# connector_fridge.net
KiCad netlist of a schematic drawn in Altium Designer
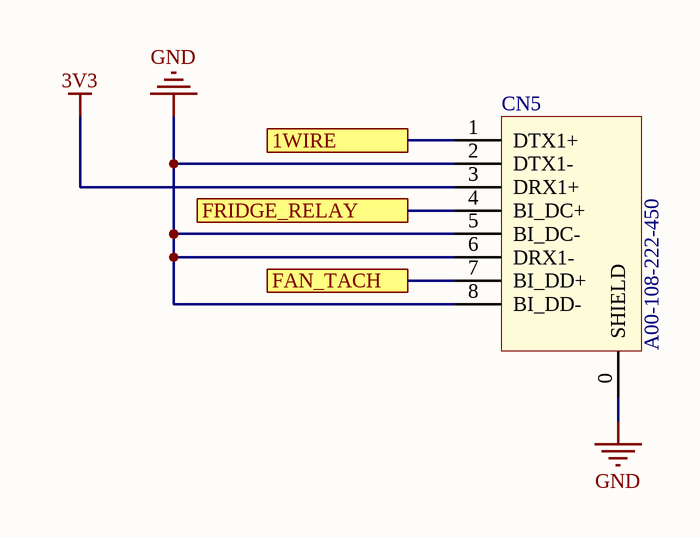
[diagram p0: connector_fridge.SchDoc]

(export (version "E")
  (design (tool "Eeschema 10.0.6"))
  (components
    (comp (ref "CN5")
      (value "CONN_RJ45_TOP_A00-108-222-450")
      (footprint "RJ45 TOP ENTRY EDAC A00-108-222-450")
      (description "CONN, RJ-45, 1-PORT, 8-POS, VERT, 0.76um GOLD, TH")
      (fields (field (name "MFG") "EDAC Inc") (field (name "MFG P/N") "A00-108-222-450"))
      (libsource (lib "AltiumReleaseLibDB") (part "CONN_RJ45_TOP_A00-108-222-450"))
    )
  )
  (nets
    (net (code "1") (name "/1WIRE") (class "Default")
      (node (ref "CN5") (pin "1") (pinfunction "DTX1+_1") (pintype "passive"))
    )
    (net (code "2") (name "/FAN_TACH") (class "Default")
      (node (ref "CN5") (pin "7") (pinfunction "BI_DD+_7") (pintype "passive"))
    )
    (net (code "3") (name "/FRIDGE_RELAY") (class "Default")
      (node (ref "CN5") (pin "4") (pinfunction "BI_DC+_4") (pintype "passive"))
    )
    (net (code "4") (name "3V3") (class "Default")
      (node (ref "CN5") (pin "3") (pinfunction "DRX1+_3") (pintype "passive"))
    )
    (net (code "5") (name "GND") (class "Default")
      (node (ref "CN5") (pin "0") (pinfunction "SHIELD_0") (pintype "passive"))
      (node (ref "CN5") (pin "2") (pinfunction "DTX1-_2") (pintype "passive"))
      (node (ref "CN5") (pin "5") (pinfunction "BI_DC-_5") (pintype "passive"))
      (node (ref "CN5") (pin "6") (pinfunction "DRX1-_6") (pintype "passive"))
      (node (ref "CN5") (pin "8") (pinfunction "BI_DD-_8") (pintype "passive"))
    )
  )
)
